# pocketwatch.net
KiCad netlist of a schematic drawn in EAGLE
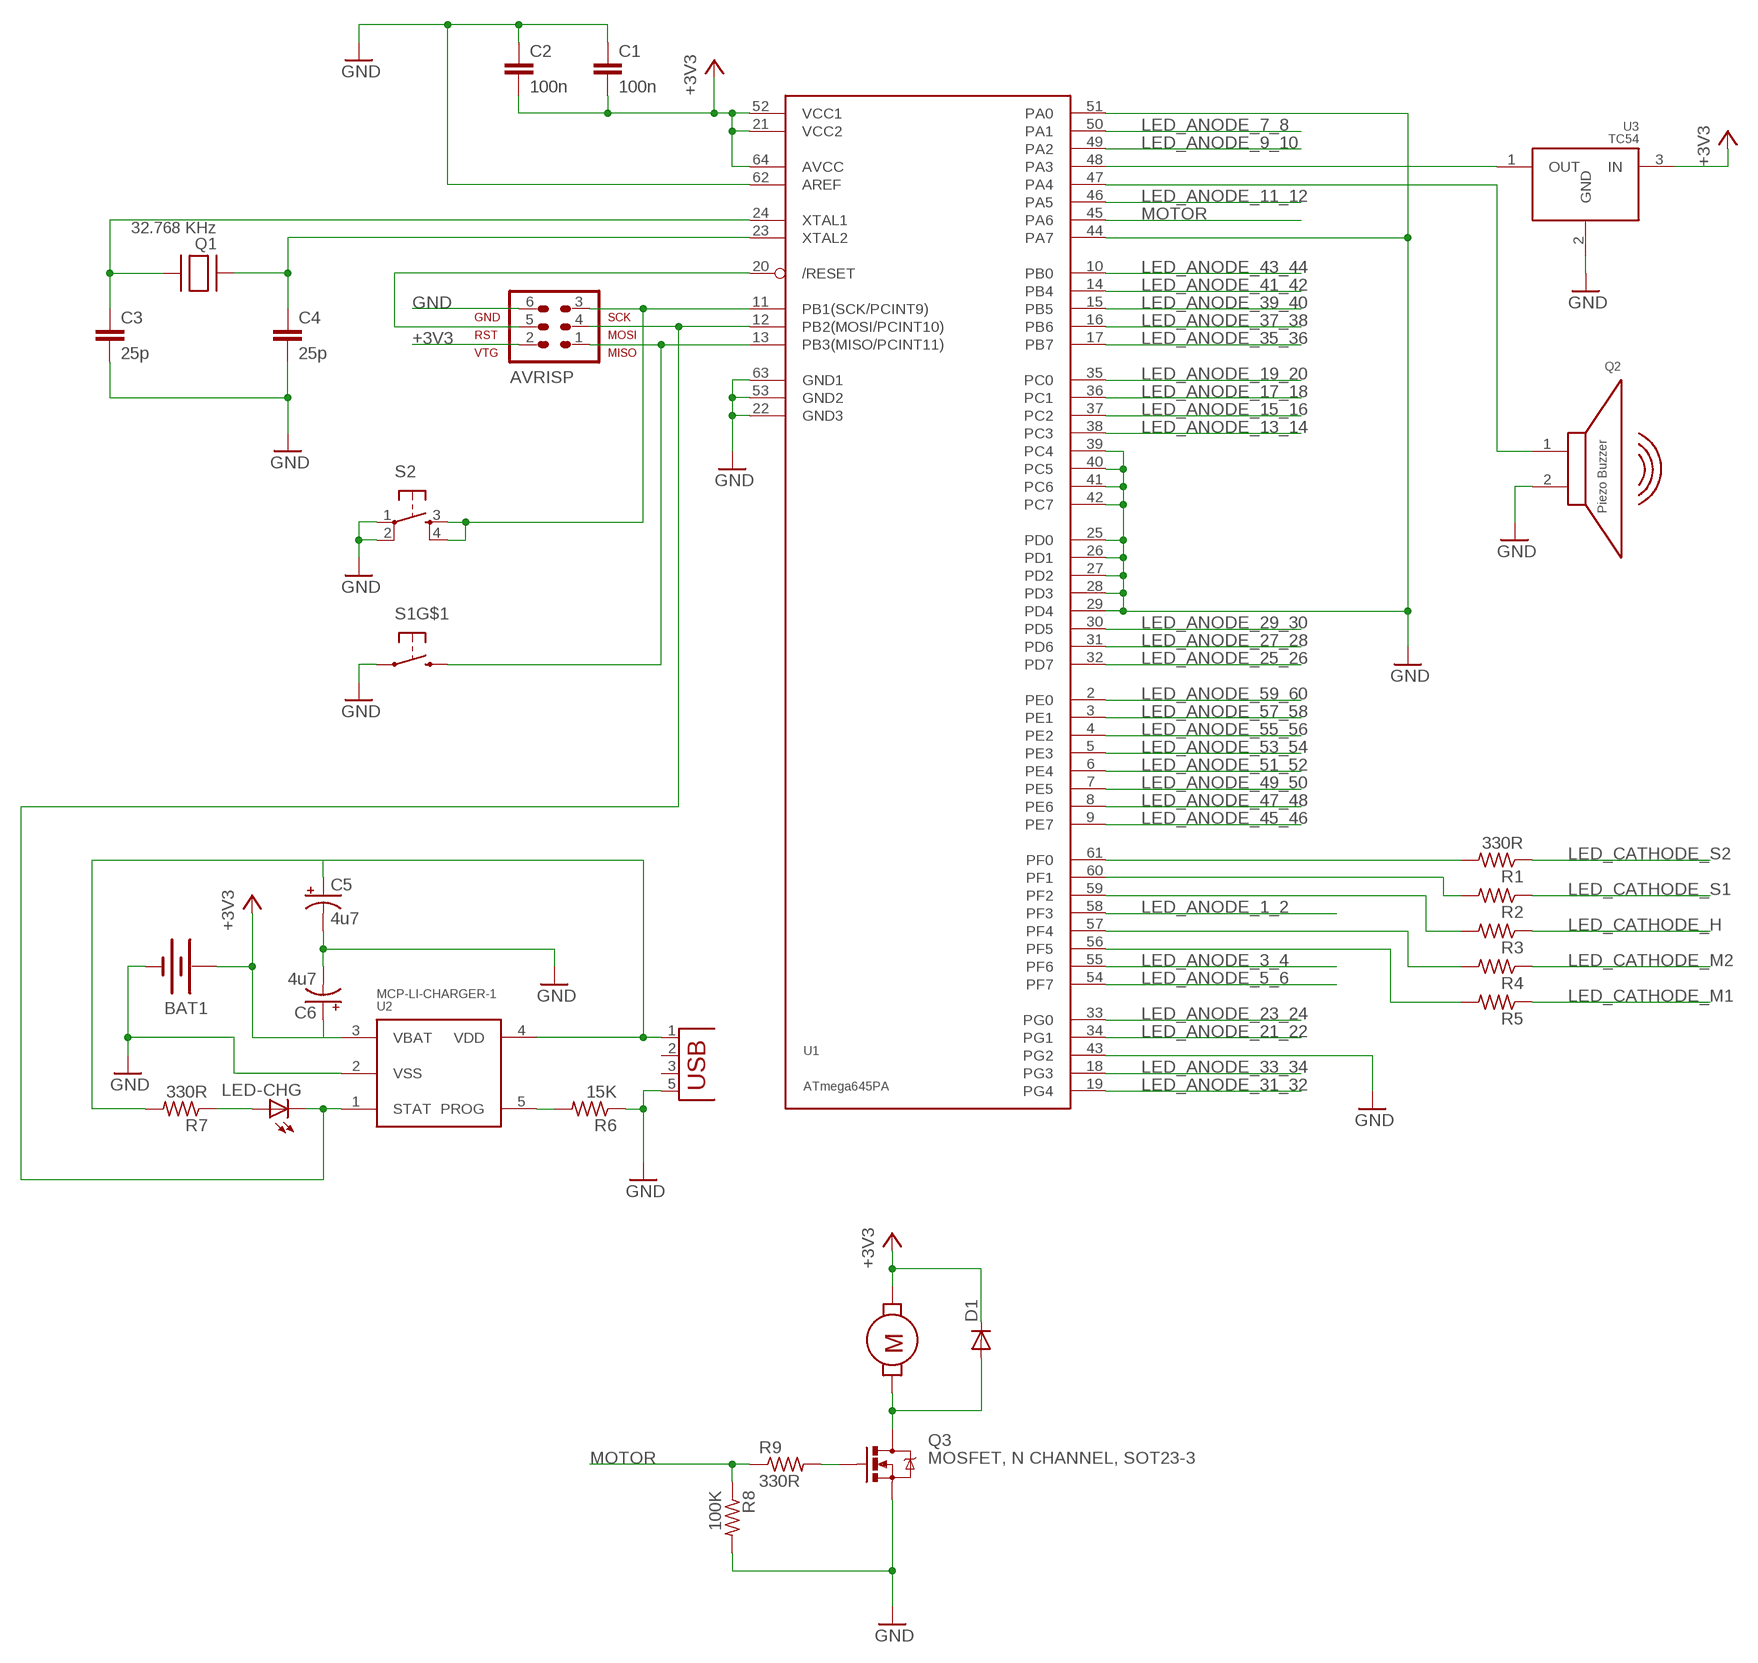
[diagram p0: schematic, sheet 1]
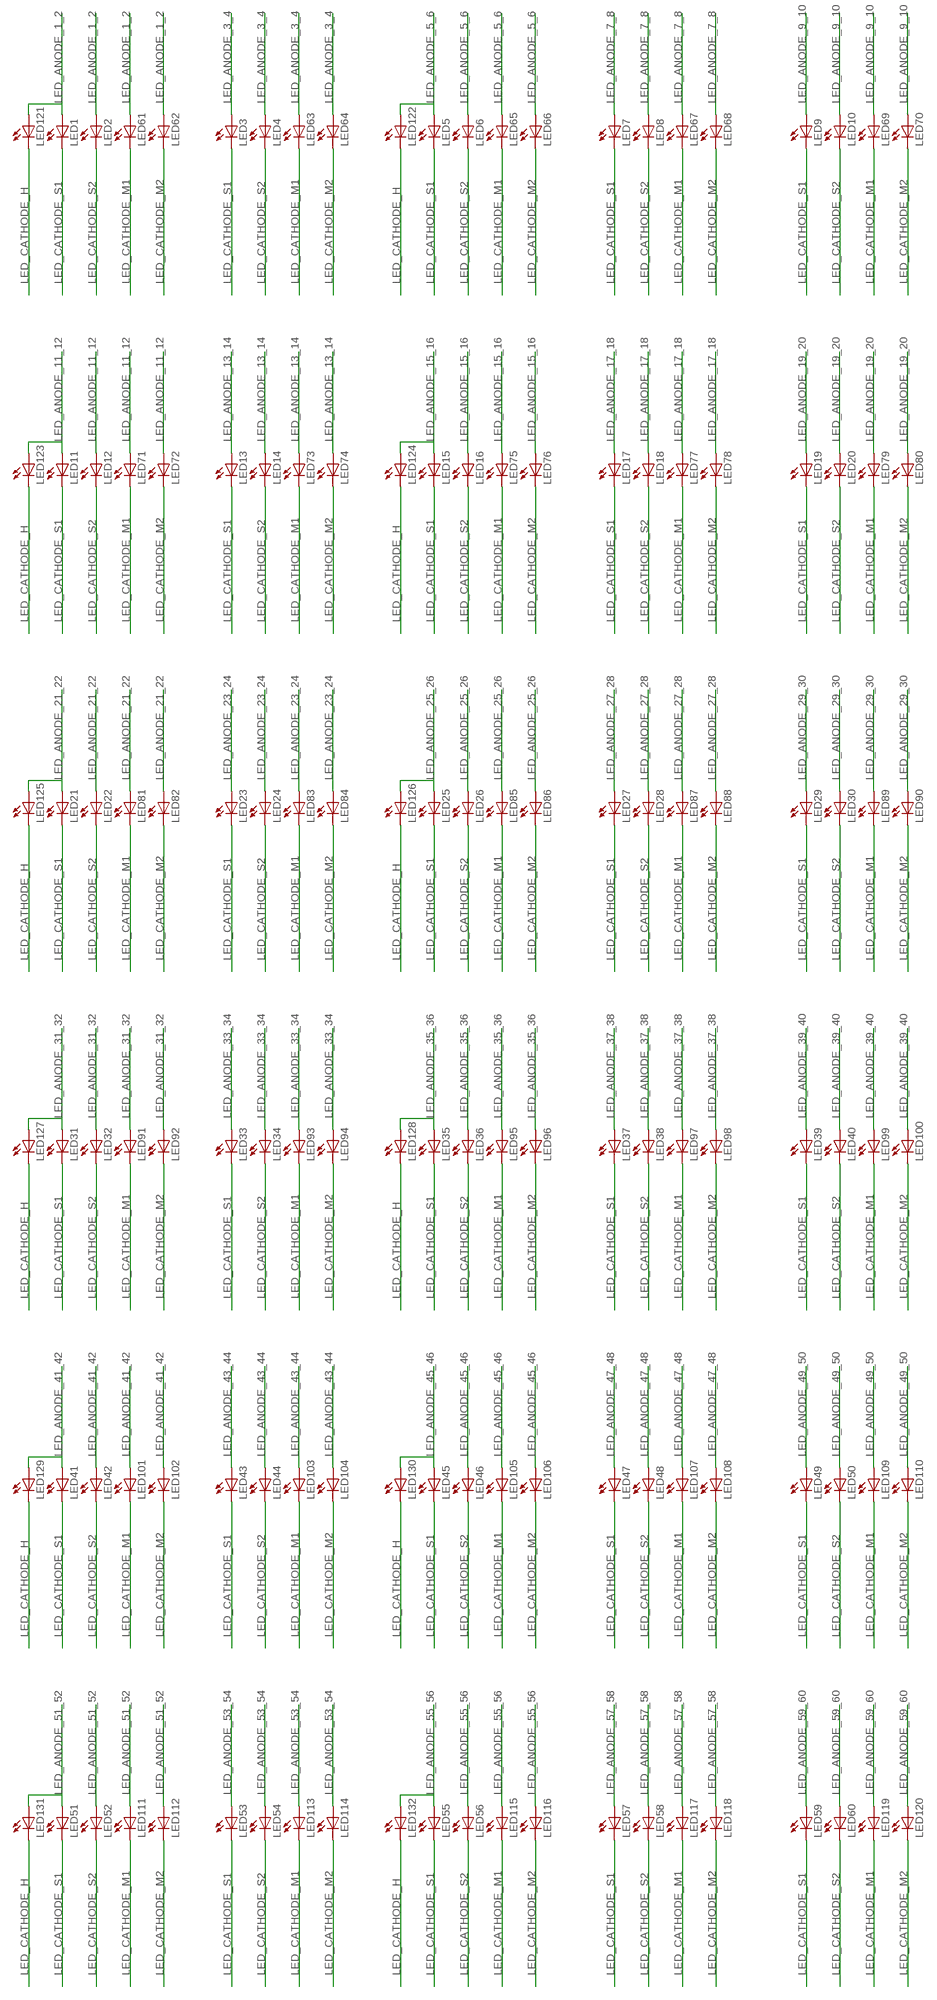
[diagram p1: schematic, sheet 2]

(export (version "E")
  (design (tool "Eeschema 10.0.6"))
  (components
    (comp (ref "LED1")
      (value "LED_CHIPLED_0603_VIA_C")
      (footprint "eagle-import:CHIPLED_0603_VIA_C")
      (libsource (lib "eagle-import") (part "LED_CHIPLED_0603_VIA_C"))
    )
    (comp (ref "LED2")
      (value "LED_CHIPLED_0603_VIA_C")
      (footprint "eagle-import:CHIPLED_0603_VIA_C")
      (libsource (lib "eagle-import") (part "LED_CHIPLED_0603_VIA_C"))
    )
    (comp (ref "LED3")
      (value "LED_CHIPLED_0603_VIA_C")
      (footprint "eagle-import:CHIPLED_0603_VIA_C")
      (libsource (lib "eagle-import") (part "LED_CHIPLED_0603_VIA_C"))
    )
    (comp (ref "LED4")
      (value "LED_CHIPLED_0603_VIA_C")
      (footprint "eagle-import:CHIPLED_0603_VIA_C")
      (libsource (lib "eagle-import") (part "LED_CHIPLED_0603_VIA_C"))
    )
    (comp (ref "LED5")
      (value "LED_CHIPLED_0603_VIA_C")
      (footprint "eagle-import:CHIPLED_0603_VIA_C")
      (libsource (lib "eagle-import") (part "LED_CHIPLED_0603_VIA_C"))
    )
    (comp (ref "LED6")
      (value "LED_CHIPLED_0603_VIA_C")
      (footprint "eagle-import:CHIPLED_0603_VIA_C")
      (libsource (lib "eagle-import") (part "LED_CHIPLED_0603_VIA_C"))
    )
    (comp (ref "LED7")
      (value "LED_CHIPLED_0603_VIA_C")
      (footprint "eagle-import:CHIPLED_0603_VIA_C")
      (libsource (lib "eagle-import") (part "LED_CHIPLED_0603_VIA_C"))
    )
    (comp (ref "LED8")
      (value "LED_CHIPLED_0603_VIA_C")
      (footprint "eagle-import:CHIPLED_0603_VIA_C")
      (libsource (lib "eagle-import") (part "LED_CHIPLED_0603_VIA_C"))
    )
    (comp (ref "LED9")
      (value "LED_CHIPLED_0603_VIA_C")
      (footprint "eagle-import:CHIPLED_0603_VIA_C")
      (libsource (lib "eagle-import") (part "LED_CHIPLED_0603_VIA_C"))
    )
    (comp (ref "LED10")
      (value "LED_CHIPLED_0603_VIA_C")
      (footprint "eagle-import:CHIPLED_0603_VIA_C")
      (libsource (lib "eagle-import") (part "LED_CHIPLED_0603_VIA_C"))
    )
    (comp (ref "LED11")
      (value "LED_CHIPLED_0603_VIA_C")
      (footprint "eagle-import:CHIPLED_0603_VIA_C")
      (libsource (lib "eagle-import") (part "LED_CHIPLED_0603_VIA_C"))
    )
    (comp (ref "LED12")
      (value "LED_CHIPLED_0603_VIA_C")
      (footprint "eagle-import:CHIPLED_0603_VIA_C")
      (libsource (lib "eagle-import") (part "LED_CHIPLED_0603_VIA_C"))
    )
    (comp (ref "LED13")
      (value "LED_CHIPLED_0603_VIA_C")
      (footprint "eagle-import:CHIPLED_0603_VIA_C")
      (libsource (lib "eagle-import") (part "LED_CHIPLED_0603_VIA_C"))
    )
    (comp (ref "LED14")
      (value "LED_CHIPLED_0603_VIA_C")
      (footprint "eagle-import:CHIPLED_0603_VIA_C")
      (libsource (lib "eagle-import") (part "LED_CHIPLED_0603_VIA_C"))
    )
    (comp (ref "LED15")
      (value "LED_CHIPLED_0603_VIA_C")
      (footprint "eagle-import:CHIPLED_0603_VIA_C")
      (libsource (lib "eagle-import") (part "LED_CHIPLED_0603_VIA_C"))
    )
    (comp (ref "LED16")
      (value "LED_CHIPLED_0603_VIA_C")
      (footprint "eagle-import:CHIPLED_0603_VIA_C")
      (libsource (lib "eagle-import") (part "LED_CHIPLED_0603_VIA_C"))
    )
    (comp (ref "LED17")
      (value "LED_CHIPLED_0603_VIA_C")
      (footprint "eagle-import:CHIPLED_0603_VIA_C")
      (libsource (lib "eagle-import") (part "LED_CHIPLED_0603_VIA_C"))
    )
    (comp (ref "LED18")
      (value "LED_CHIPLED_0603_VIA_C")
      (footprint "eagle-import:CHIPLED_0603_VIA_C")
      (libsource (lib "eagle-import") (part "LED_CHIPLED_0603_VIA_C"))
    )
    (comp (ref "LED19")
      (value "LED_CHIPLED_0603_VIA_C")
      (footprint "eagle-import:CHIPLED_0603_VIA_C")
      (libsource (lib "eagle-import") (part "LED_CHIPLED_0603_VIA_C"))
    )
    (comp (ref "LED20")
      (value "LED_CHIPLED_0603_VIA_C")
      (footprint "eagle-import:CHIPLED_0603_VIA_C")
      (libsource (lib "eagle-import") (part "LED_CHIPLED_0603_VIA_C"))
    )
    (comp (ref "LED21")
      (value "LED_CHIPLED_0603_VIA_C")
      (footprint "eagle-import:CHIPLED_0603_VIA_C")
      (libsource (lib "eagle-import") (part "LED_CHIPLED_0603_VIA_C"))
    )
    (comp (ref "LED22")
      (value "LED_CHIPLED_0603_VIA_C")
      (footprint "eagle-import:CHIPLED_0603_VIA_C")
      (libsource (lib "eagle-import") (part "LED_CHIPLED_0603_VIA_C"))
    )
    (comp (ref "LED23")
      (value "LED_CHIPLED_0603_VIA_C")
      (footprint "eagle-import:CHIPLED_0603_VIA_C")
      (libsource (lib "eagle-import") (part "LED_CHIPLED_0603_VIA_C"))
    )
    (comp (ref "LED24")
      (value "LED_CHIPLED_0603_VIA_C")
      (footprint "eagle-import:CHIPLED_0603_VIA_C")
      (libsource (lib "eagle-import") (part "LED_CHIPLED_0603_VIA_C"))
    )
    (comp (ref "LED25")
      (value "LED_CHIPLED_0603_VIA_C")
      (footprint "eagle-import:CHIPLED_0603_VIA_C")
      (libsource (lib "eagle-import") (part "LED_CHIPLED_0603_VIA_C"))
    )
    (comp (ref "LED26")
      (value "LED_CHIPLED_0603_VIA_C")
      (footprint "eagle-import:CHIPLED_0603_VIA_C")
      (libsource (lib "eagle-import") (part "LED_CHIPLED_0603_VIA_C"))
    )
    (comp (ref "LED27")
      (value "LED_CHIPLED_0603_VIA_C")
      (footprint "eagle-import:CHIPLED_0603_VIA_C")
      (libsource (lib "eagle-import") (part "LED_CHIPLED_0603_VIA_C"))
    )
    (comp (ref "LED28")
      (value "LED_CHIPLED_0603_VIA_C")
      (footprint "eagle-import:CHIPLED_0603_VIA_C")
      (libsource (lib "eagle-import") (part "LED_CHIPLED_0603_VIA_C"))
    )
    (comp (ref "LED29")
      (value "LED_CHIPLED_0603_VIA_C")
      (footprint "eagle-import:CHIPLED_0603_VIA_C")
      (libsource (lib "eagle-import") (part "LED_CHIPLED_0603_VIA_C"))
    )
    (comp (ref "LED30")
      (value "LED_CHIPLED_0603_VIA_C")
      (footprint "eagle-import:CHIPLED_0603_VIA_C")
      (libsource (lib "eagle-import") (part "LED_CHIPLED_0603_VIA_C"))
    )
    (comp (ref "LED31")
      (value "LED_CHIPLED_0603_VIA_C")
      (footprint "eagle-import:CHIPLED_0603_VIA_C")
      (libsource (lib "eagle-import") (part "LED_CHIPLED_0603_VIA_C"))
    )
    (comp (ref "LED32")
      (value "LED_CHIPLED_0603_VIA_C")
      (footprint "eagle-import:CHIPLED_0603_VIA_C")
      (libsource (lib "eagle-import") (part "LED_CHIPLED_0603_VIA_C"))
    )
    (comp (ref "LED33")
      (value "LED_CHIPLED_0603_VIA_C")
      (footprint "eagle-import:CHIPLED_0603_VIA_C")
      (libsource (lib "eagle-import") (part "LED_CHIPLED_0603_VIA_C"))
    )
    (comp (ref "LED34")
      (value "LED_CHIPLED_0603_VIA_C")
      (footprint "eagle-import:CHIPLED_0603_VIA_C")
      (libsource (lib "eagle-import") (part "LED_CHIPLED_0603_VIA_C"))
    )
    (comp (ref "LED35")
      (value "LED_CHIPLED_0603_VIA_C")
      (footprint "eagle-import:CHIPLED_0603_VIA_C")
      (libsource (lib "eagle-import") (part "LED_CHIPLED_0603_VIA_C"))
    )
    (comp (ref "LED36")
      (value "LED_CHIPLED_0603_VIA_C")
      (footprint "eagle-import:CHIPLED_0603_VIA_C")
      (libsource (lib "eagle-import") (part "LED_CHIPLED_0603_VIA_C"))
    )
    (comp (ref "LED37")
      (value "LED_CHIPLED_0603_VIA_C")
      (footprint "eagle-import:CHIPLED_0603_VIA_C")
      (libsource (lib "eagle-import") (part "LED_CHIPLED_0603_VIA_C"))
    )
    (comp (ref "LED38")
      (value "LED_CHIPLED_0603_VIA_C")
      (footprint "eagle-import:CHIPLED_0603_VIA_C")
      (libsource (lib "eagle-import") (part "LED_CHIPLED_0603_VIA_C"))
    )
    (comp (ref "LED39")
      (value "LED_CHIPLED_0603_VIA_C")
      (footprint "eagle-import:CHIPLED_0603_VIA_C")
      (libsource (lib "eagle-import") (part "LED_CHIPLED_0603_VIA_C"))
    )
    (comp (ref "LED40")
      (value "LED_CHIPLED_0603_VIA_C")
      (footprint "eagle-import:CHIPLED_0603_VIA_C")
      (libsource (lib "eagle-import") (part "LED_CHIPLED_0603_VIA_C"))
    )
    (comp (ref "LED41")
      (value "LED_CHIPLED_0603_VIA_C")
      (footprint "eagle-import:CHIPLED_0603_VIA_C")
      (libsource (lib "eagle-import") (part "LED_CHIPLED_0603_VIA_C"))
    )
    (comp (ref "LED42")
      (value "LED_CHIPLED_0603_VIA_C")
      (footprint "eagle-import:CHIPLED_0603_VIA_C")
      (libsource (lib "eagle-import") (part "LED_CHIPLED_0603_VIA_C"))
    )
    (comp (ref "LED43")
      (value "LED_CHIPLED_0603_VIA_C")
      (footprint "eagle-import:CHIPLED_0603_VIA_C")
      (libsource (lib "eagle-import") (part "LED_CHIPLED_0603_VIA_C"))
    )
    (comp (ref "LED44")
      (value "LED_CHIPLED_0603_VIA_C")
      (footprint "eagle-import:CHIPLED_0603_VIA_C")
      (libsource (lib "eagle-import") (part "LED_CHIPLED_0603_VIA_C"))
    )
    (comp (ref "LED45")
      (value "LED_CHIPLED_0603_VIA_C")
      (footprint "eagle-import:CHIPLED_0603_VIA_C")
      (libsource (lib "eagle-import") (part "LED_CHIPLED_0603_VIA_C"))
    )
    (comp (ref "LED46")
      (value "LED_CHIPLED_0603_VIA_C")
      (footprint "eagle-import:CHIPLED_0603_VIA_C")
      (libsource (lib "eagle-import") (part "LED_CHIPLED_0603_VIA_C"))
    )
    (comp (ref "LED47")
      (value "LED_CHIPLED_0603_VIA_C")
      (footprint "eagle-import:CHIPLED_0603_VIA_C")
      (libsource (lib "eagle-import") (part "LED_CHIPLED_0603_VIA_C"))
    )
    (comp (ref "LED48")
      (value "LED_CHIPLED_0603_VIA_C")
      (footprint "eagle-import:CHIPLED_0603_VIA_C")
      (libsource (lib "eagle-import") (part "LED_CHIPLED_0603_VIA_C"))
    )
    (comp (ref "LED49")
      (value "LED_CHIPLED_0603_VIA_C")
      (footprint "eagle-import:CHIPLED_0603_VIA_C")
      (libsource (lib "eagle-import") (part "LED_CHIPLED_0603_VIA_C"))
    )
    (comp (ref "LED50")
      (value "LED_CHIPLED_0603_VIA_C")
      (footprint "eagle-import:CHIPLED_0603_VIA_C")
      (libsource (lib "eagle-import") (part "LED_CHIPLED_0603_VIA_C"))
    )
    (comp (ref "LED51")
      (value "LED_CHIPLED_0603_VIA_C")
      (footprint "eagle-import:CHIPLED_0603_VIA_C")
      (libsource (lib "eagle-import") (part "LED_CHIPLED_0603_VIA_C"))
    )
    (comp (ref "LED52")
      (value "LED_CHIPLED_0603_VIA_C")
      (footprint "eagle-import:CHIPLED_0603_VIA_C")
      (libsource (lib "eagle-import") (part "LED_CHIPLED_0603_VIA_C"))
    )
    (comp (ref "LED53")
      (value "LED_CHIPLED_0603_VIA_C")
      (footprint "eagle-import:CHIPLED_0603_VIA_C")
      (libsource (lib "eagle-import") (part "LED_CHIPLED_0603_VIA_C"))
    )
    (comp (ref "LED54")
      (value "LED_CHIPLED_0603_VIA_C")
      (footprint "eagle-import:CHIPLED_0603_VIA_C")
      (libsource (lib "eagle-import") (part "LED_CHIPLED_0603_VIA_C"))
    )
    (comp (ref "LED55")
      (value "LED_CHIPLED_0603_VIA_C")
      (footprint "eagle-import:CHIPLED_0603_VIA_C")
      (libsource (lib "eagle-import") (part "LED_CHIPLED_0603_VIA_C"))
    )
    (comp (ref "LED56")
      (value "LED_CHIPLED_0603_VIA_C")
      (footprint "eagle-import:CHIPLED_0603_VIA_C")
      (libsource (lib "eagle-import") (part "LED_CHIPLED_0603_VIA_C"))
    )
    (comp (ref "LED57")
      (value "LED_CHIPLED_0603_VIA_C")
      (footprint "eagle-import:CHIPLED_0603_VIA_C")
      (libsource (lib "eagle-import") (part "LED_CHIPLED_0603_VIA_C"))
    )
    (comp (ref "LED58")
      (value "LED_CHIPLED_0603_VIA_C")
      (footprint "eagle-import:CHIPLED_0603_VIA_C")
      (libsource (lib "eagle-import") (part "LED_CHIPLED_0603_VIA_C"))
    )
    (comp (ref "LED59")
      (value "LED_CHIPLED_0603_VIA_C")
      (footprint "eagle-import:CHIPLED_0603_VIA_C")
      (libsource (lib "eagle-import") (part "LED_CHIPLED_0603_VIA_C"))
    )
    (comp (ref "LED60")
      (value "LED_CHIPLED_0603_VIA_C")
      (footprint "eagle-import:CHIPLED_0603_VIA_C")
      (libsource (lib "eagle-import") (part "LED_CHIPLED_0603_VIA_C"))
    )
    (comp (ref "LED61")
      (value "LED_CHIPLED_0603_VIA_C")
      (footprint "eagle-import:CHIPLED_0603_VIA_C")
      (libsource (lib "eagle-import") (part "LED_CHIPLED_0603_VIA_C"))
    )
    (comp (ref "LED62")
      (value "LED_CHIPLED_0603_VIA_C")
      (footprint "eagle-import:CHIPLED_0603_VIA_C")
      (libsource (lib "eagle-import") (part "LED_CHIPLED_0603_VIA_C"))
    )
    (comp (ref "LED63")
      (value "LED_CHIPLED_0603_VIA_C")
      (footprint "eagle-import:CHIPLED_0603_VIA_C")
      (libsource (lib "eagle-import") (part "LED_CHIPLED_0603_VIA_C"))
    )
    (comp (ref "LED64")
      (value "LED_CHIPLED_0603_VIA_C")
      (footprint "eagle-import:CHIPLED_0603_VIA_C")
      (libsource (lib "eagle-import") (part "LED_CHIPLED_0603_VIA_C"))
    )
    (comp (ref "LED65")
      (value "LED_CHIPLED_0603_VIA_C")
      (footprint "eagle-import:CHIPLED_0603_VIA_C")
      (libsource (lib "eagle-import") (part "LED_CHIPLED_0603_VIA_C"))
    )
    (comp (ref "LED66")
      (value "LED_CHIPLED_0603_VIA_C")
      (footprint "eagle-import:CHIPLED_0603_VIA_C")
      (libsource (lib "eagle-import") (part "LED_CHIPLED_0603_VIA_C"))
    )
    (comp (ref "LED67")
      (value "LED_CHIPLED_0603_VIA_C")
      (footprint "eagle-import:CHIPLED_0603_VIA_C")
      (libsource (lib "eagle-import") (part "LED_CHIPLED_0603_VIA_C"))
    )
    (comp (ref "LED68")
      (value "LED_CHIPLED_0603_VIA_C")
      (footprint "eagle-import:CHIPLED_0603_VIA_C")
      (libsource (lib "eagle-import") (part "LED_CHIPLED_0603_VIA_C"))
    )
    (comp (ref "LED69")
      (value "LED_CHIPLED_0603_VIA_C")
      (footprint "eagle-import:CHIPLED_0603_VIA_C")
      (libsource (lib "eagle-import") (part "LED_CHIPLED_0603_VIA_C"))
    )
    (comp (ref "LED70")
      (value "LED_CHIPLED_0603_VIA_C")
      (footprint "eagle-import:CHIPLED_0603_VIA_C")
      (libsource (lib "eagle-import") (part "LED_CHIPLED_0603_VIA_C"))
    )
    (comp (ref "LED71")
      (value "LED_CHIPLED_0603_VIA_C")
      (footprint "eagle-import:CHIPLED_0603_VIA_C")
      (libsource (lib "eagle-import") (part "LED_CHIPLED_0603_VIA_C"))
    )
    (comp (ref "LED72")
      (value "LED_CHIPLED_0603_VIA_C")
      (footprint "eagle-import:CHIPLED_0603_VIA_C")
      (libsource (lib "eagle-import") (part "LED_CHIPLED_0603_VIA_C"))
    )
    (comp (ref "LED73")
      (value "LED_CHIPLED_0603_VIA_C")
      (footprint "eagle-import:CHIPLED_0603_VIA_C")
      (libsource (lib "eagle-import") (part "LED_CHIPLED_0603_VIA_C"))
    )
    (comp (ref "LED74")
      (value "LED_CHIPLED_0603_VIA_C")
      (footprint "eagle-import:CHIPLED_0603_VIA_C")
      (libsource (lib "eagle-import") (part "LED_CHIPLED_0603_VIA_C"))
    )
    (comp (ref "LED75")
      (value "LED_CHIPLED_0603_VIA_C")
      (footprint "eagle-import:CHIPLED_0603_VIA_C")
      (libsource (lib "eagle-import") (part "LED_CHIPLED_0603_VIA_C"))
    )
    (comp (ref "LED76")
      (value "LED_CHIPLED_0603_VIA_C")
      (footprint "eagle-import:CHIPLED_0603_VIA_C")
      (libsource (lib "eagle-import") (part "LED_CHIPLED_0603_VIA_C"))
    )
    (comp (ref "LED77")
      (value "LED_CHIPLED_0603_VIA_C")
      (footprint "eagle-import:CHIPLED_0603_VIA_C")
      (libsource (lib "eagle-import") (part "LED_CHIPLED_0603_VIA_C"))
    )
    (comp (ref "LED78")
      (value "LED_CHIPLED_0603_VIA_C")
      (footprint "eagle-import:CHIPLED_0603_VIA_C")
      (libsource (lib "eagle-import") (part "LED_CHIPLED_0603_VIA_C"))
    )
    (comp (ref "LED79")
      (value "LED_CHIPLED_0603_VIA_C")
      (footprint "eagle-import:CHIPLED_0603_VIA_C")
      (libsource (lib "eagle-import") (part "LED_CHIPLED_0603_VIA_C"))
    )
    (comp (ref "LED80")
      (value "LED_CHIPLED_0603_VIA_C")
      (footprint "eagle-import:CHIPLED_0603_VIA_C")
      (libsource (lib "eagle-import") (part "LED_CHIPLED_0603_VIA_C"))
    )
    (comp (ref "LED81")
      (value "LED_CHIPLED_0603_VIA_C")
      (footprint "eagle-import:CHIPLED_0603_VIA_C")
      (libsource (lib "eagle-import") (part "LED_CHIPLED_0603_VIA_C"))
    )
    (comp (ref "LED82")
      (value "LED_CHIPLED_0603_VIA_C")
      (footprint "eagle-import:CHIPLED_0603_VIA_C")
      (libsource (lib "eagle-import") (part "LED_CHIPLED_0603_VIA_C"))
    )
    (comp (ref "LED83")
      (value "LED_CHIPLED_0603_VIA_C")
      (footprint "eagle-import:CHIPLED_0603_VIA_C")
      (libsource (lib "eagle-import") (part "LED_CHIPLED_0603_VIA_C"))
    )
    (comp (ref "LED84")
      (value "LED_CHIPLED_0603_VIA_C")
      (footprint "eagle-import:CHIPLED_0603_VIA_C")
      (libsource (lib "eagle-import") (part "LED_CHIPLED_0603_VIA_C"))
    )
    (comp (ref "LED85")
      (value "LED_CHIPLED_0603_VIA_C")
      (footprint "eagle-import:CHIPLED_0603_VIA_C")
      (libsource (lib "eagle-import") (part "LED_CHIPLED_0603_VIA_C"))
    )
    (comp (ref "LED86")
      (value "LED_CHIPLED_0603_VIA_C")
      (footprint "eagle-import:CHIPLED_0603_VIA_C")
      (libsource (lib "eagle-import") (part "LED_CHIPLED_0603_VIA_C"))
    )
    (comp (ref "LED87")
      (value "LED_CHIPLED_0603_VIA_C")
      (footprint "eagle-import:CHIPLED_0603_VIA_C")
      (libsource (lib "eagle-import") (part "LED_CHIPLED_0603_VIA_C"))
    )
    (comp (ref "LED88")
      (value "LED_CHIPLED_0603_VIA_C")
      (footprint "eagle-import:CHIPLED_0603_VIA_C")
      (libsource (lib "eagle-import") (part "LED_CHIPLED_0603_VIA_C"))
    )
    (comp (ref "LED89")
      (value "LED_CHIPLED_0603_VIA_C")
      (footprint "eagle-import:CHIPLED_0603_VIA_C")
      (libsource (lib "eagle-import") (part "LED_CHIPLED_0603_VIA_C"))
    )
    (comp (ref "LED90")
      (value "LED_CHIPLED_0603_VIA_C")
      (footprint "eagle-import:CHIPLED_0603_VIA_C")
      (libsource (lib "eagle-import") (part "LED_CHIPLED_0603_VIA_C"))
    )
    (comp (ref "LED91")
      (value "LED_CHIPLED_0603_VIA_C")
      (footprint "eagle-import:CHIPLED_0603_VIA_C")
      (libsource (lib "eagle-import") (part "LED_CHIPLED_0603_VIA_C"))
    )
    (comp (ref "LED92")
      (value "LED_CHIPLED_0603_VIA_C")
      (footprint "eagle-import:CHIPLED_0603_VIA_C")
      (libsource (lib "eagle-import") (part "LED_CHIPLED_0603_VIA_C"))
    )
    (comp (ref "LED93")
      (value "LED_CHIPLED_0603_VIA_C")
      (footprint "eagle-import:CHIPLED_0603_VIA_C")
      (libsource (lib "eagle-import") (part "LED_CHIPLED_0603_VIA_C"))
    )
    (comp (ref "LED94")
      (value "LED_CHIPLED_0603_VIA_C")
      (footprint "eagle-import:CHIPLED_0603_VIA_C")
      (libsource (lib "eagle-import") (part "LED_CHIPLED_0603_VIA_C"))
    )
    (comp (ref "LED95")
      (value "LED_CHIPLED_0603_VIA_C")
      (footprint "eagle-import:CHIPLED_0603_VIA_C")
      (libsource (lib "eagle-import") (part "LED_CHIPLED_0603_VIA_C"))
    )
    (comp (ref "LED96")
      (value "LED_CHIPLED_0603_VIA_C")
      (footprint "eagle-import:CHIPLED_0603_VIA_C")
      (libsource (lib "eagle-import") (part "LED_CHIPLED_0603_VIA_C"))
    )
    (comp (ref "LED97")
      (value "LED_CHIPLED_0603_VIA_C")
      (footprint "eagle-import:CHIPLED_0603_VIA_C")
      (libsource (lib "eagle-import") (part "LED_CHIPLED_0603_VIA_C"))
    )
    (comp (ref "LED98")
      (value "LED_CHIPLED_0603_VIA_C")
      (footprint "eagle-import:CHIPLED_0603_VIA_C")
      (libsource (lib "eagle-import") (part "LED_CHIPLED_0603_VIA_C"))
    )
    (comp (ref "LED99")
      (value "LED_CHIPLED_0603_VIA_C")
      (footprint "eagle-import:CHIPLED_0603_VIA_C")
      (libsource (lib "eagle-import") (part "LED_CHIPLED_0603_VIA_C"))
    )
    (comp (ref "LED100")
      (value "LED_CHIPLED_0603_VIA_C")
      (footprint "eagle-import:CHIPLED_0603_VIA_C")
      (libsource (lib "eagle-import") (part "LED_CHIPLED_0603_VIA_C"))
    )
    (comp (ref "LED101")
      (value "LED_CHIPLED_0603_VIA_C")
      (footprint "eagle-import:CHIPLED_0603_VIA_C")
      (libsource (lib "eagle-import") (part "LED_CHIPLED_0603_VIA_C"))
    )
    (comp (ref "LED102")
      (value "LED_CHIPLED_0603_VIA_C")
      (footprint "eagle-import:CHIPLED_0603_VIA_C")
      (libsource (lib "eagle-import") (part "LED_CHIPLED_0603_VIA_C"))
    )
    (comp (ref "LED103")
      (value "LED_CHIPLED_0603_VIA_C")
      (footprint "eagle-import:CHIPLED_0603_VIA_C")
      (libsource (lib "eagle-import") (part "LED_CHIPLED_0603_VIA_C"))
    )
    (comp (ref "LED104")
      (value "LED_CHIPLED_0603_VIA_C")
      (footprint "eagle-import:CHIPLED_0603_VIA_C")
      (libsource (lib "eagle-import") (part "LED_CHIPLED_0603_VIA_C"))
    )
    (comp (ref "LED105")
      (value "LED_CHIPLED_0603_VIA_C")
      (footprint "eagle-import:CHIPLED_0603_VIA_C")
      (libsource (lib "eagle-import") (part "LED_CHIPLED_0603_VIA_C"))
    )
    (comp (ref "LED106")
      (value "LED_CHIPLED_0603_VIA_C")
      (footprint "eagle-import:CHIPLED_0603_VIA_C")
      (libsource (lib "eagle-import") (part "LED_CHIPLED_0603_VIA_C"))
    )
    (comp (ref "LED107")
      (value "LED_CHIPLED_0603_VIA_C")
      (footprint "eagle-import:CHIPLED_0603_VIA_C")
      (libsource (lib "eagle-import") (part "LED_CHIPLED_0603_VIA_C"))
    )
    (comp (ref "LED108")
      (value "LED_CHIPLED_0603_VIA_C")
      (footprint "eagle-import:CHIPLED_0603_VIA_C")
      (libsource (lib "eagle-import") (part "LED_CHIPLED_0603_VIA_C"))
    )
    (comp (ref "LED109")
      (value "LED_CHIPLED_0603_VIA_C")
      (footprint "eagle-import:CHIPLED_0603_VIA_C")
      (libsource (lib "eagle-import") (part "LED_CHIPLED_0603_VIA_C"))
    )
    (comp (ref "LED110")
      (value "LED_CHIPLED_0603_VIA_C")
      (footprint "eagle-import:CHIPLED_0603_VIA_C")
      (libsource (lib "eagle-import") (part "LED_CHIPLED_0603_VIA_C"))
    )
    (comp (ref "LED111")
      (value "LED_CHIPLED_0603_VIA_C")
      (footprint "eagle-import:CHIPLED_0603_VIA_C")
      (libsource (lib "eagle-import") (part "LED_CHIPLED_0603_VIA_C"))
    )
    (comp (ref "LED112")
      (value "LED_CHIPLED_0603_VIA_C")
      (footprint "eagle-import:CHIPLED_0603_VIA_C")
      (libsource (lib "eagle-import") (part "LED_CHIPLED_0603_VIA_C"))
    )
    (comp (ref "LED113")
      (value "LED_CHIPLED_0603_VIA_C")
      (footprint "eagle-import:CHIPLED_0603_VIA_C")
      (libsource (lib "eagle-import") (part "LED_CHIPLED_0603_VIA_C"))
    )
    (comp (ref "LED114")
      (value "LED_CHIPLED_0603_VIA_C")
      (footprint "eagle-import:CHIPLED_0603_VIA_C")
      (libsource (lib "eagle-import") (part "LED_CHIPLED_0603_VIA_C"))
    )
    (comp (ref "LED115")
      (value "LED_CHIPLED_0603_VIA_C")
      (footprint "eagle-import:CHIPLED_0603_VIA_C")
      (libsource (lib "eagle-import") (part "LED_CHIPLED_0603_VIA_C"))
    )
    (comp (ref "LED116")
      (value "LED_CHIPLED_0603_VIA_C")
      (footprint "eagle-import:CHIPLED_0603_VIA_C")
      (libsource (lib "eagle-import") (part "LED_CHIPLED_0603_VIA_C"))
    )
    (comp (ref "LED117")
      (value "LED_CHIPLED_0603_VIA_C")
      (footprint "eagle-import:CHIPLED_0603_VIA_C")
      (libsource (lib "eagle-import") (part "LED_CHIPLED_0603_VIA_C"))
    )
    (comp (ref "LED118")
      (value "LED_CHIPLED_0603_VIA_C")
      (footprint "eagle-import:CHIPLED_0603_VIA_C")
      (libsource (lib "eagle-import") (part "LED_CHIPLED_0603_VIA_C"))
    )
    (comp (ref "LED119")
      (value "LED_CHIPLED_0603_VIA_C")
      (footprint "eagle-import:CHIPLED_0603_VIA_C")
      (libsource (lib "eagle-import") (part "LED_CHIPLED_0603_VIA_C"))
    )
    (comp (ref "LED120")
      (value "LED_CHIPLED_0603_VIA_C")
      (footprint "eagle-import:CHIPLED_0603_VIA_C")
      (libsource (lib "eagle-import") (part "LED_CHIPLED_0603_VIA_C"))
    )
    (comp (ref "LED121")
      (value "LED_CHIPLED_0603_VIA_C")
      (footprint "eagle-import:CHIPLED_0603_VIA_C")
      (libsource (lib "eagle-import") (part "LED_CHIPLED_0603_VIA_C"))
    )
    (comp (ref "LED122")
      (value "LED_CHIPLED_0603_VIA_C")
      (footprint "eagle-import:CHIPLED_0603_VIA_C")
      (libsource (lib "eagle-import") (part "LED_CHIPLED_0603_VIA_C"))
    )
    (comp (ref "LED123")
      (value "LED_CHIPLED_0603_VIA_C")
      (footprint "eagle-import:CHIPLED_0603_VIA_C")
      (libsource (lib "eagle-import") (part "LED_CHIPLED_0603_VIA_C"))
    )
    (comp (ref "LED124")
      (value "LED_CHIPLED_0603_VIA_C")
      (footprint "eagle-import:CHIPLED_0603_VIA_C")
      (libsource (lib "eagle-import") (part "LED_CHIPLED_0603_VIA_C"))
    )
    (comp (ref "LED125")
      (value "LED_CHIPLED_0603_VIA_C")
      (footprint "eagle-import:CHIPLED_0603_VIA_C")
      (libsource (lib "eagle-import") (part "LED_CHIPLED_0603_VIA_C"))
    )
    (comp (ref "LED126")
      (value "LED_CHIPLED_0603_VIA_C")
      (footprint "eagle-import:CHIPLED_0603_VIA_C")
      (libsource (lib "eagle-import") (part "LED_CHIPLED_0603_VIA_C"))
    )
    (comp (ref "LED127")
      (value "LED_CHIPLED_0603_VIA_C")
      (footprint "eagle-import:CHIPLED_0603_VIA_C")
      (libsource (lib "eagle-import") (part "LED_CHIPLED_0603_VIA_C"))
    )
    (comp (ref "LED128")
      (value "LED_CHIPLED_0603_VIA_C")
      (footprint "eagle-import:CHIPLED_0603_VIA_C")
      (libsource (lib "eagle-import") (part "LED_CHIPLED_0603_VIA_C"))
    )
    (comp (ref "LED129")
      (value "LED_CHIPLED_0603_VIA_C")
      (footprint "eagle-import:CHIPLED_0603_VIA_C")
      (libsource (lib "eagle-import") (part "LED_CHIPLED_0603_VIA_C"))
    )
    (comp (ref "LED130")
      (value "LED_CHIPLED_0603_VIA_C")
      (footprint "eagle-import:CHIPLED_0603_VIA_C")
      (libsource (lib "eagle-import") (part "LED_CHIPLED_0603_VIA_C"))
    )
    (comp (ref "LED131")
      (value "LED_CHIPLED_0603_VIA_C")
      (footprint "eagle-import:CHIPLED_0603_VIA_C")
      (libsource (lib "eagle-import") (part "LED_CHIPLED_0603_VIA_C"))
    )
    (comp (ref "LED132")
      (value "LED_CHIPLED_0603_VIA_C")
      (footprint "eagle-import:CHIPLED_0603_VIA_C")
      (libsource (lib "eagle-import") (part "LED_CHIPLED_0603_VIA_C"))
    )
    (comp (ref "AVRISP")
      (value "AVR-ISP-6")
      (footprint "eagle-import:AVR-ISP-6")
      (libsource (lib "eagle-import") (part "AVR-ISP-6"))
    )
    (comp (ref "BAT1")
      (value "BATTERY245MM")
      (footprint "eagle-import:BATTCON_245MM")
      (libsource (lib "eagle-import") (part "BATTERY245MM"))
    )
    (comp (ref "C1")
      (value "100n")
      (footprint "eagle-import:C0603")
      (libsource (lib "eagle-import") (part "C-EUC0603"))
    )
    (comp (ref "C2")
      (value "100n")
      (footprint "eagle-import:C0603")
      (libsource (lib "eagle-import") (part "C-EUC0603"))
    )
    (comp (ref "C3")
      (value "25p")
      (footprint "eagle-import:C0603")
      (libsource (lib "eagle-import") (part "C-EUC0603"))
    )
    (comp (ref "C4")
      (value "25p")
      (footprint "eagle-import:C0603")
      (libsource (lib "eagle-import") (part "C-EUC0603"))
    )
    (comp (ref "C5")
      (value "4u7")
      (footprint "eagle-import:SMC_A")
      (libsource (lib "eagle-import") (part "CPOL-USSMCA"))
    )
    (comp (ref "C6")
      (value "4u7")
      (footprint "eagle-import:SMC_A")
      (libsource (lib "eagle-import") (part "CPOL-USSMCA"))
    )
    (comp (ref "D1")
      (value "DIODESOD")
      (footprint "eagle-import:SOD-323")
      (libsource (lib "eagle-import") (part "DIODESOD"))
    )
    (comp (ref "LED-CHG")
      (value "LEDCHIPLED_0603")
      (footprint "eagle-import:CHIPLED_0603")
      (libsource (lib "eagle-import") (part "LEDCHIPLED_0603"))
    )
    (comp (ref "M1")
      (value "MOTOR")
      (footprint "eagle-import:VIBRATION-MOTOR")
      (libsource (lib "eagle-import") (part "MOTOR"))
    )
    (comp (ref "Q1")
      (value "32.768 KHz")
      (footprint "eagle-import:XTAL_2SMD")
      (libsource (lib "eagle-import") (part "XTALSMD1"))
    )
    (comp (ref "Q2")
      (value "BUZZER")
      (footprint "eagle-import:BUZZER_1")
      (libsource (lib "eagle-import") (part "BUZZER"))
    )
    (comp (ref "Q3")
      (value "MOSFET, N CHANNEL, SOT23-3")
      (footprint "eagle-import:SOT23-3")
      (libsource (lib "eagle-import") (part "MOSFET-NCHANNELSMD"))
    )
    (comp (ref "R1")
      (value "330R")
      (footprint "eagle-import:R0603")
      (libsource (lib "eagle-import") (part "R-US_R0603"))
    )
    (comp (ref "R2")
      (value "R-US_R0603")
      (footprint "eagle-import:R0603")
      (libsource (lib "eagle-import") (part "R-US_R0603"))
    )
    (comp (ref "R3")
      (value "R-US_R0603")
      (footprint "eagle-import:R0603")
      (libsource (lib "eagle-import") (part "R-US_R0603"))
    )
    (comp (ref "R4")
      (value "R-US_R0603")
      (footprint "eagle-import:R0603")
      (libsource (lib "eagle-import") (part "R-US_R0603"))
    )
    (comp (ref "R5")
      (value "R-US_R0603")
      (footprint "eagle-import:R0603")
      (libsource (lib "eagle-import") (part "R-US_R0603"))
    )
    (comp (ref "R6")
      (value "15K")
      (footprint "eagle-import:R0603")
      (libsource (lib "eagle-import") (part "R-US_R0603"))
    )
    (comp (ref "R7")
      (value "330R")
      (footprint "eagle-import:R0603")
      (libsource (lib "eagle-import") (part "R-US_R0603"))
    )
    (comp (ref "R8")
      (value "100K")
      (footprint "eagle-import:R0603")
      (libsource (lib "eagle-import") (part "R-US_R0603"))
    )
    (comp (ref "R9")
      (value "330R")
      (footprint "eagle-import:R0603")
      (libsource (lib "eagle-import") (part "R-US_R0603"))
    )
    (comp (ref "S1")
      (value "TAC_SWITCH_SINGLE")
      (footprint "eagle-import:TAC_SWITCH_SIDE_1")
      (libsource (lib "eagle-import") (part "TAC_SWITCH_SINGLE"))
    )
    (comp (ref "S2")
      (value "TAC_SWITCHSMD")
      (footprint "eagle-import:TACTILE_SWITCH_SMD")
      (libsource (lib "eagle-import") (part "TAC_SWITCHSMD"))
    )
    (comp (ref "U1")
      (value "ATmega645PA")
      (footprint "eagle-import:TQFP64")
      (libsource (lib "eagle-import") (part "ATMEGA645TQFP64"))
    )
    (comp (ref "U2")
      (value "MCP-LI-CHARGER-1")
      (footprint "eagle-import:SOT23-5")
      (libsource (lib "eagle-import") (part "MCP-LI-CHARGER-1"))
    )
    (comp (ref "U3")
      (value "TC54")
      (footprint "eagle-import:SOT23-3")
      (libsource (lib "eagle-import") (part "TC54"))
    )
    (comp (ref "X1")
      (value "USB-MICRO_B")
      (footprint "eagle-import:USB_MICRO_B")
      (libsource (lib "eagle-import") (part "USB-MICRO_B"))
    )
  )
  (nets
    (net (code "1") (name "+3V3") (class "Default")
      (node (ref "AVRISP") (pin "2") (pinfunction "VTG_2") (pintype "passive"))
      (node (ref "BAT1") (pin "1") (pinfunction "+_1") (pintype "power_in"))
      (node (ref "C1") (pin "2") (pinfunction "2_2") (pintype "passive"))
      (node (ref "C2") (pin "2") (pinfunction "2_2") (pintype "passive"))
      (node (ref "C6") (pin "+") (pinfunction "+_+") (pintype "passive"))
      (node (ref "D1") (pin "1") (pinfunction "C_1") (pintype "passive"))
      (node (ref "M1") (pin "P$1") (pinfunction "P$1_P$1") (pintype "bidirectional"))
      (node (ref "U1") (pin "21") (pinfunction "VCC2_21") (pintype "power_in"))
      (node (ref "U1") (pin "52") (pinfunction "VCC1_52") (pintype "power_in"))
      (node (ref "U1") (pin "64") (pinfunction "AVCC_64") (pintype "power_in"))
      (node (ref "U2") (pin "3") (pinfunction "VBAT_3") (pintype "power_in"))
      (node (ref "U3") (pin "3") (pinfunction "IN_3") (pintype "bidirectional"))
    )
    (net (code "2") (name "GND") (class "Default")
      (node (ref "AVRISP") (pin "6") (pinfunction "GND_6") (pintype "passive"))
      (node (ref "BAT1") (pin "2") (pinfunction "-_2") (pintype "power_in"))
      (node (ref "C1") (pin "1") (pinfunction "1_1") (pintype "passive"))
      (node (ref "C2") (pin "1") (pinfunction "1_1") (pintype "passive"))
      (node (ref "C3") (pin "2") (pinfunction "2_2") (pintype "passive"))
      (node (ref "C4") (pin "2") (pinfunction "2_2") (pintype "passive"))
      (node (ref "C5") (pin "-") (pinfunction "-_-") (pintype "passive"))
      (node (ref "C6") (pin "-") (pinfunction "-_-") (pintype "passive"))
      (node (ref "Q2") (pin "2") (pinfunction "P$2_2") (pintype "bidirectional"))
      (node (ref "Q3") (pin "2") (pinfunction "S_2") (pintype "passive"))
      (node (ref "R6") (pin "1") (pinfunction "1_1") (pintype "passive"))
      (node (ref "R8") (pin "2") (pinfunction "2_2") (pintype "passive"))
      (node (ref "S1") (pin "G1") (pinfunction "P$1_G1") (pintype "bidirectional"))
      (node (ref "S1") (pin "G2") (pinfunction "P$1_G2") (pintype "bidirectional"))
      (node (ref "S1") (pin "P$2") (pinfunction "1_P$2") (pintype "passive"))
      (node (ref "S2") (pin "1") (pinfunction "1_1") (pintype "passive"))
      (node (ref "S2") (pin "2") (pinfunction "2_2") (pintype "passive"))
      (node (ref "U1") (pin "22") (pinfunction "GND3_22") (pintype "power_in"))
      (node (ref "U1") (pin "25") (pinfunction "PD0_25") (pintype "bidirectional"))
      (node (ref "U1") (pin "26") (pinfunction "PD1_26") (pintype "bidirectional"))
      (node (ref "U1") (pin "27") (pinfunction "PD2_27") (pintype "bidirectional"))
      (node (ref "U1") (pin "28") (pinfunction "PD3_28") (pintype "bidirectional"))
      (node (ref "U1") (pin "29") (pinfunction "PD4_29") (pintype "bidirectional"))
      (node (ref "U1") (pin "39") (pinfunction "PC4_39") (pintype "bidirectional"))
      (node (ref "U1") (pin "40") (pinfunction "PC5_40") (pintype "bidirectional"))
      (node (ref "U1") (pin "41") (pinfunction "PC6_41") (pintype "bidirectional"))
      (node (ref "U1") (pin "42") (pinfunction "PC7_42") (pintype "bidirectional"))
      (node (ref "U1") (pin "43") (pinfunction "PG2_43") (pintype "bidirectional"))
      (node (ref "U1") (pin "44") (pinfunction "PA7_44") (pintype "bidirectional"))
      (node (ref "U1") (pin "51") (pinfunction "PA0_51") (pintype "bidirectional"))
      (node (ref "U1") (pin "53") (pinfunction "GND2_53") (pintype "power_in"))
      (node (ref "U1") (pin "62") (pinfunction "AREF_62") (pintype "power_in"))
      (node (ref "U1") (pin "63") (pinfunction "GND1_63") (pintype "power_in"))
      (node (ref "U2") (pin "2") (pinfunction "VSS_2") (pintype "power_in"))
      (node (ref "U3") (pin "2") (pinfunction "GND_2") (pintype "bidirectional"))
      (node (ref "X1") (pin "5") (pinfunction "GND_5") (pintype "bidirectional"))
      (node (ref "X1") (pin "P$3") (pinfunction "P$1_P$3") (pintype "bidirectional"))
      (node (ref "X1") (pin "P$4") (pinfunction "P$1_P$4") (pintype "bidirectional"))
      (node (ref "X1") (pin "P$7") (pinfunction "P$1_P$7") (pintype "bidirectional"))
      (node (ref "X1") (pin "P$8") (pinfunction "P$1_P$8") (pintype "bidirectional"))
    )
    (net (code "3") (name "LED_ANODE_1_2") (class "Default")
      (node (ref "LED1") (pin "A") (pinfunction "A_A") (pintype "passive"))
      (node (ref "LED121") (pin "A") (pinfunction "A_A") (pintype "passive"))
      (node (ref "LED2") (pin "A") (pinfunction "A_A") (pintype "passive"))
      (node (ref "LED61") (pin "A") (pinfunction "A_A") (pintype "passive"))
      (node (ref "LED62") (pin "A") (pinfunction "A_A") (pintype "passive"))
      (node (ref "U1") (pin "58") (pinfunction "PF3_58") (pintype "bidirectional"))
    )
    (net (code "4") (name "LED_ANODE_3_4") (class "Default")
      (node (ref "LED3") (pin "A") (pinfunction "A_A") (pintype "passive"))
      (node (ref "LED4") (pin "A") (pinfunction "A_A") (pintype "passive"))
      (node (ref "LED63") (pin "A") (pinfunction "A_A") (pintype "passive"))
      (node (ref "LED64") (pin "A") (pinfunction "A_A") (pintype "passive"))
      (node (ref "U1") (pin "55") (pinfunction "PF6_55") (pintype "bidirectional"))
    )
    (net (code "5") (name "LED_ANODE_5_6") (class "Default")
      (node (ref "LED122") (pin "A") (pinfunction "A_A") (pintype "passive"))
      (node (ref "LED5") (pin "A") (pinfunction "A_A") (pintype "passive"))
      (node (ref "LED6") (pin "A") (pinfunction "A_A") (pintype "passive"))
      (node (ref "LED65") (pin "A") (pinfunction "A_A") (pintype "passive"))
      (node (ref "LED66") (pin "A") (pinfunction "A_A") (pintype "passive"))
      (node (ref "U1") (pin "54") (pinfunction "PF7_54") (pintype "bidirectional"))
    )
    (net (code "6") (name "LED_ANODE_7_8") (class "Default")
      (node (ref "LED67") (pin "A") (pinfunction "A_A") (pintype "passive"))
      (node (ref "LED68") (pin "A") (pinfunction "A_A") (pintype "passive"))
      (node (ref "LED7") (pin "A") (pinfunction "A_A") (pintype "passive"))
      (node (ref "LED8") (pin "A") (pinfunction "A_A") (pintype "passive"))
      (node (ref "U1") (pin "50") (pinfunction "PA1_50") (pintype "bidirectional"))
    )
    (net (code "7") (name "LED_ANODE_9_10") (class "Default")
      (node (ref "LED10") (pin "A") (pinfunction "A_A") (pintype "passive"))
      (node (ref "LED69") (pin "A") (pinfunction "A_A") (pintype "passive"))
      (node (ref "LED70") (pin "A") (pinfunction "A_A") (pintype "passive"))
      (node (ref "LED9") (pin "A") (pinfunction "A_A") (pintype "passive"))
      (node (ref "U1") (pin "49") (pinfunction "PA2_49") (pintype "bidirectional"))
    )
    (net (code "8") (name "LED_ANODE_11_12") (class "Default")
      (node (ref "LED11") (pin "A") (pinfunction "A_A") (pintype "passive"))
      (node (ref "LED12") (pin "A") (pinfunction "A_A") (pintype "passive"))
      (node (ref "LED123") (pin "A") (pinfunction "A_A") (pintype "passive"))
      (node (ref "LED71") (pin "A") (pinfunction "A_A") (pintype "passive"))
      (node (ref "LED72") (pin "A") (pinfunction "A_A") (pintype "passive"))
      (node (ref "U1") (pin "46") (pinfunction "PA5_46") (pintype "bidirectional"))
    )
    (net (code "9") (name "LED_ANODE_13_14") (class "Default")
      (node (ref "LED13") (pin "A") (pinfunction "A_A") (pintype "passive"))
      (node (ref "LED14") (pin "A") (pinfunction "A_A") (pintype "passive"))
      (node (ref "LED73") (pin "A") (pinfunction "A_A") (pintype "passive"))
      (node (ref "LED74") (pin "A") (pinfunction "A_A") (pintype "passive"))
      (node (ref "U1") (pin "38") (pinfunction "PC3_38") (pintype "bidirectional"))
    )
    (net (code "10") (name "LED_ANODE_15_16") (class "Default")
      (node (ref "LED124") (pin "A") (pinfunction "A_A") (pintype "passive"))
      (node (ref "LED15") (pin "A") (pinfunction "A_A") (pintype "passive"))
      (node (ref "LED16") (pin "A") (pinfunction "A_A") (pintype "passive"))
      (node (ref "LED75") (pin "A") (pinfunction "A_A") (pintype "passive"))
      (node (ref "LED76") (pin "A") (pinfunction "A_A") (pintype "passive"))
      (node (ref "U1") (pin "37") (pinfunction "PC2_37") (pintype "bidirectional"))
    )
    (net (code "11") (name "LED_ANODE_17_18") (class "Default")
      (node (ref "LED17") (pin "A") (pinfunction "A_A") (pintype "passive"))
      (node (ref "LED18") (pin "A") (pinfunction "A_A") (pintype "passive"))
      (node (ref "LED77") (pin "A") (pinfunction "A_A") (pintype "passive"))
      (node (ref "LED78") (pin "A") (pinfunction "A_A") (pintype "passive"))
      (node (ref "U1") (pin "36") (pinfunction "PC1_36") (pintype "bidirectional"))
    )
    (net (code "12") (name "LED_ANODE_19_20") (class "Default")
      (node (ref "LED19") (pin "A") (pinfunction "A_A") (pintype "passive"))
      (node (ref "LED20") (pin "A") (pinfunction "A_A") (pintype "passive"))
      (node (ref "LED79") (pin "A") (pinfunction "A_A") (pintype "passive"))
      (node (ref "LED80") (pin "A") (pinfunction "A_A") (pintype "passive"))
      (node (ref "U1") (pin "35") (pinfunction "PC0_35") (pintype "bidirectional"))
    )
    (net (code "13") (name "LED_ANODE_21_22") (class "Default")
      (node (ref "LED125") (pin "A") (pinfunction "A_A") (pintype "passive"))
      (node (ref "LED21") (pin "A") (pinfunction "A_A") (pintype "passive"))
      (node (ref "LED22") (pin "A") (pinfunction "A_A") (pintype "passive"))
      (node (ref "LED81") (pin "A") (pinfunction "A_A") (pintype "passive"))
      (node (ref "LED82") (pin "A") (pinfunction "A_A") (pintype "passive"))
      (node (ref "U1") (pin "34") (pinfunction "PG1_34") (pintype "bidirectional"))
    )
    (net (code "14") (name "LED_ANODE_23_24") (class "Default")
      (node (ref "LED23") (pin "A") (pinfunction "A_A") (pintype "passive"))
      (node (ref "LED24") (pin "A") (pinfunction "A_A") (pintype "passive"))
      (node (ref "LED83") (pin "A") (pinfunction "A_A") (pintype "passive"))
      (node (ref "LED84") (pin "A") (pinfunction "A_A") (pintype "passive"))
      (node (ref "U1") (pin "33") (pinfunction "PG0_33") (pintype "bidirectional"))
    )
    (net (code "15") (name "LED_ANODE_25_26") (class "Default")
      (node (ref "LED126") (pin "A") (pinfunction "A_A") (pintype "passive"))
      (node (ref "LED25") (pin "A") (pinfunction "A_A") (pintype "passive"))
      (node (ref "LED26") (pin "A") (pinfunction "A_A") (pintype "passive"))
      (node (ref "LED85") (pin "A") (pinfunction "A_A") (pintype "passive"))
      (node (ref "LED86") (pin "A") (pinfunction "A_A") (pintype "passive"))
      (node (ref "U1") (pin "32") (pinfunction "PD7_32") (pintype "bidirectional"))
    )
    (net (code "16") (name "LED_ANODE_27_28") (class "Default")
      (node (ref "LED27") (pin "A") (pinfunction "A_A") (pintype "passive"))
      (node (ref "LED28") (pin "A") (pinfunction "A_A") (pintype "passive"))
      (node (ref "LED87") (pin "A") (pinfunction "A_A") (pintype "passive"))
      (node (ref "LED88") (pin "A") (pinfunction "A_A") (pintype "passive"))
      (node (ref "U1") (pin "31") (pinfunction "PD6_31") (pintype "bidirectional"))
    )
    (net (code "17") (name "LED_ANODE_29_30") (class "Default")
      (node (ref "LED29") (pin "A") (pinfunction "A_A") (pintype "passive"))
      (node (ref "LED30") (pin "A") (pinfunction "A_A") (pintype "passive"))
      (node (ref "LED89") (pin "A") (pinfunction "A_A") (pintype "passive"))
      (node (ref "LED90") (pin "A") (pinfunction "A_A") (pintype "passive"))
      (node (ref "U1") (pin "30") (pinfunction "PD5_30") (pintype "bidirectional"))
    )
    (net (code "18") (name "LED_ANODE_31_32") (class "Default")
      (node (ref "LED127") (pin "A") (pinfunction "A_A") (pintype "passive"))
      (node (ref "LED31") (pin "A") (pinfunction "A_A") (pintype "passive"))
      (node (ref "LED32") (pin "A") (pinfunction "A_A") (pintype "passive"))
      (node (ref "LED91") (pin "A") (pinfunction "A_A") (pintype "passive"))
      (node (ref "LED92") (pin "A") (pinfunction "A_A") (pintype "passive"))
      (node (ref "U1") (pin "19") (pinfunction "PG4_19") (pintype "bidirectional"))
    )
    (net (code "19") (name "LED_ANODE_33_34") (class "Default")
      (node (ref "LED33") (pin "A") (pinfunction "A_A") (pintype "passive"))
      (node (ref "LED34") (pin "A") (pinfunction "A_A") (pintype "passive"))
      (node (ref "LED93") (pin "A") (pinfunction "A_A") (pintype "passive"))
      (node (ref "LED94") (pin "A") (pinfunction "A_A") (pintype "passive"))
      (node (ref "U1") (pin "18") (pinfunction "PG3_18") (pintype "bidirectional"))
    )
    (net (code "20") (name "LED_ANODE_35_36") (class "Default")
      (node (ref "LED128") (pin "A") (pinfunction "A_A") (pintype "passive"))
      (node (ref "LED35") (pin "A") (pinfunction "A_A") (pintype "passive"))
      (node (ref "LED36") (pin "A") (pinfunction "A_A") (pintype "passive"))
      (node (ref "LED95") (pin "A") (pinfunction "A_A") (pintype "passive"))
      (node (ref "LED96") (pin "A") (pinfunction "A_A") (pintype "passive"))
      (node (ref "U1") (pin "17") (pinfunction "PB7_17") (pintype "bidirectional"))
    )
    (net (code "21") (name "LED_ANODE_37_38") (class "Default")
      (node (ref "LED37") (pin "A") (pinfunction "A_A") (pintype "passive"))
      (node (ref "LED38") (pin "A") (pinfunction "A_A") (pintype "passive"))
      (node (ref "LED97") (pin "A") (pinfunction "A_A") (pintype "passive"))
      (node (ref "LED98") (pin "A") (pinfunction "A_A") (pintype "passive"))
      (node (ref "U1") (pin "16") (pinfunction "PB6_16") (pintype "bidirectional"))
    )
    (net (code "22") (name "LED_ANODE_39_40") (class "Default")
      (node (ref "LED100") (pin "A") (pinfunction "A_A") (pintype "passive"))
      (node (ref "LED39") (pin "A") (pinfunction "A_A") (pintype "passive"))
      (node (ref "LED40") (pin "A") (pinfunction "A_A") (pintype "passive"))
      (node (ref "LED99") (pin "A") (pinfunction "A_A") (pintype "passive"))
      (node (ref "U1") (pin "15") (pinfunction "PB5_15") (pintype "bidirectional"))
    )
    (net (code "23") (name "LED_ANODE_41_42") (class "Default")
      (node (ref "LED101") (pin "A") (pinfunction "A_A") (pintype "passive"))
      (node (ref "LED102") (pin "A") (pinfunction "A_A") (pintype "passive"))
      (node (ref "LED129") (pin "A") (pinfunction "A_A") (pintype "passive"))
      (node (ref "LED41") (pin "A") (pinfunction "A_A") (pintype "passive"))
      (node (ref "LED42") (pin "A") (pinfunction "A_A") (pintype "passive"))
      (node (ref "U1") (pin "14") (pinfunction "PB4_14") (pintype "bidirectional"))
    )
    (net (code "24") (name "LED_ANODE_43_44") (class "Default")
      (node (ref "LED103") (pin "A") (pinfunction "A_A") (pintype "passive"))
      (node (ref "LED104") (pin "A") (pinfunction "A_A") (pintype "passive"))
      (node (ref "LED43") (pin "A") (pinfunction "A_A") (pintype "passive"))
      (node (ref "LED44") (pin "A") (pinfunction "A_A") (pintype "passive"))
      (node (ref "U1") (pin "10") (pinfunction "PB0_10") (pintype "bidirectional"))
    )
    (net (code "25") (name "LED_ANODE_45_46") (class "Default")
      (node (ref "LED105") (pin "A") (pinfunction "A_A") (pintype "passive"))
      (node (ref "LED106") (pin "A") (pinfunction "A_A") (pintype "passive"))
      (node (ref "LED130") (pin "A") (pinfunction "A_A") (pintype "passive"))
      (node (ref "LED45") (pin "A") (pinfunction "A_A") (pintype "passive"))
      (node (ref "LED46") (pin "A") (pinfunction "A_A") (pintype "passive"))
      (node (ref "U1") (pin "9") (pinfunction "PE7_9") (pintype "bidirectional"))
    )
    (net (code "26") (name "LED_ANODE_47_48") (class "Default")
      (node (ref "LED107") (pin "A") (pinfunction "A_A") (pintype "passive"))
      (node (ref "LED108") (pin "A") (pinfunction "A_A") (pintype "passive"))
      (node (ref "LED47") (pin "A") (pinfunction "A_A") (pintype "passive"))
      (node (ref "LED48") (pin "A") (pinfunction "A_A") (pintype "passive"))
      (node (ref "U1") (pin "8") (pinfunction "PE6_8") (pintype "bidirectional"))
    )
    (net (code "27") (name "LED_ANODE_49_50") (class "Default")
      (node (ref "LED109") (pin "A") (pinfunction "A_A") (pintype "passive"))
      (node (ref "LED110") (pin "A") (pinfunction "A_A") (pintype "passive"))
      (node (ref "LED49") (pin "A") (pinfunction "A_A") (pintype "passive"))
      (node (ref "LED50") (pin "A") (pinfunction "A_A") (pintype "passive"))
      (node (ref "U1") (pin "7") (pinfunction "PE5_7") (pintype "bidirectional"))
    )
    (net (code "28") (name "LED_ANODE_51_52") (class "Default")
      (node (ref "LED111") (pin "A") (pinfunction "A_A") (pintype "passive"))
      (node (ref "LED112") (pin "A") (pinfunction "A_A") (pintype "passive"))
      (node (ref "LED131") (pin "A") (pinfunction "A_A") (pintype "passive"))
      (node (ref "LED51") (pin "A") (pinfunction "A_A") (pintype "passive"))
      (node (ref "LED52") (pin "A") (pinfunction "A_A") (pintype "passive"))
      (node (ref "U1") (pin "6") (pinfunction "PE4_6") (pintype "bidirectional"))
    )
    (net (code "29") (name "LED_ANODE_53_54") (class "Default")
      (node (ref "LED113") (pin "A") (pinfunction "A_A") (pintype "passive"))
      (node (ref "LED114") (pin "A") (pinfunction "A_A") (pintype "passive"))
      (node (ref "LED53") (pin "A") (pinfunction "A_A") (pintype "passive"))
      (node (ref "LED54") (pin "A") (pinfunction "A_A") (pintype "passive"))
      (node (ref "U1") (pin "5") (pinfunction "PE3_5") (pintype "bidirectional"))
    )
    (net (code "30") (name "LED_ANODE_55_56") (class "Default")
      (node (ref "LED115") (pin "A") (pinfunction "A_A") (pintype "passive"))
      (node (ref "LED116") (pin "A") (pinfunction "A_A") (pintype "passive"))
      (node (ref "LED132") (pin "A") (pinfunction "A_A") (pintype "passive"))
      (node (ref "LED55") (pin "A") (pinfunction "A_A") (pintype "passive"))
      (node (ref "LED56") (pin "A") (pinfunction "A_A") (pintype "passive"))
      (node (ref "U1") (pin "4") (pinfunction "PE2_4") (pintype "bidirectional"))
    )
    (net (code "31") (name "LED_ANODE_57_58") (class "Default")
      (node (ref "LED117") (pin "A") (pinfunction "A_A") (pintype "passive"))
      (node (ref "LED118") (pin "A") (pinfunction "A_A") (pintype "passive"))
      (node (ref "LED57") (pin "A") (pinfunction "A_A") (pintype "passive"))
      (node (ref "LED58") (pin "A") (pinfunction "A_A") (pintype "passive"))
      (node (ref "U1") (pin "3") (pinfunction "PE1_3") (pintype "bidirectional"))
    )
    (net (code "32") (name "LED_ANODE_59_60") (class "Default")
      (node (ref "LED119") (pin "A") (pinfunction "A_A") (pintype "passive"))
      (node (ref "LED120") (pin "A") (pinfunction "A_A") (pintype "passive"))
      (node (ref "LED59") (pin "A") (pinfunction "A_A") (pintype "passive"))
      (node (ref "LED60") (pin "A") (pinfunction "A_A") (pintype "passive"))
      (node (ref "U1") (pin "2") (pinfunction "PE0_2") (pintype "bidirectional"))
    )
    (net (code "33") (name "LED_CATHODE_H") (class "Default")
      (node (ref "LED121") (pin "C") (pinfunction "C_C") (pintype "passive"))
      (node (ref "LED122") (pin "C") (pinfunction "C_C") (pintype "passive"))
      (node (ref "LED123") (pin "C") (pinfunction "C_C") (pintype "passive"))
      (node (ref "LED124") (pin "C") (pinfunction "C_C") (pintype "passive"))
      (node (ref "LED125") (pin "C") (pinfunction "C_C") (pintype "passive"))
      (node (ref "LED126") (pin "C") (pinfunction "C_C") (pintype "passive"))
      (node (ref "LED127") (pin "C") (pinfunction "C_C") (pintype "passive"))
      (node (ref "LED128") (pin "C") (pinfunction "C_C") (pintype "passive"))
      (node (ref "LED129") (pin "C") (pinfunction "C_C") (pintype "passive"))
      (node (ref "LED130") (pin "C") (pinfunction "C_C") (pintype "passive"))
      (node (ref "LED131") (pin "C") (pinfunction "C_C") (pintype "passive"))
      (node (ref "LED132") (pin "C") (pinfunction "C_C") (pintype "passive"))
      (node (ref "R3") (pin "1") (pinfunction "1_1") (pintype "passive"))
    )
    (net (code "34") (name "LED_CATHODE_M1") (class "Default")
      (node (ref "LED101") (pin "C") (pinfunction "C_C") (pintype "passive"))
      (node (ref "LED103") (pin "C") (pinfunction "C_C") (pintype "passive"))
      (node (ref "LED105") (pin "C") (pinfunction "C_C") (pintype "passive"))
      (node (ref "LED107") (pin "C") (pinfunction "C_C") (pintype "passive"))
      (node (ref "LED109") (pin "C") (pinfunction "C_C") (pintype "passive"))
      (node (ref "LED111") (pin "C") (pinfunction "C_C") (pintype "passive"))
      (node (ref "LED113") (pin "C") (pinfunction "C_C") (pintype "passive"))
      (node (ref "LED115") (pin "C") (pinfunction "C_C") (pintype "passive"))
      (node (ref "LED117") (pin "C") (pinfunction "C_C") (pintype "passive"))
      (node (ref "LED119") (pin "C") (pinfunction "C_C") (pintype "passive"))
      (node (ref "LED61") (pin "C") (pinfunction "C_C") (pintype "passive"))
      (node (ref "LED63") (pin "C") (pinfunction "C_C") (pintype "passive"))
      (node (ref "LED65") (pin "C") (pinfunction "C_C") (pintype "passive"))
      (node (ref "LED67") (pin "C") (pinfunction "C_C") (pintype "passive"))
      (node (ref "LED69") (pin "C") (pinfunction "C_C") (pintype "passive"))
      (node (ref "LED71") (pin "C") (pinfunction "C_C") (pintype "passive"))
      (node (ref "LED73") (pin "C") (pinfunction "C_C") (pintype "passive"))
      (node (ref "LED75") (pin "C") (pinfunction "C_C") (pintype "passive"))
      (node (ref "LED77") (pin "C") (pinfunction "C_C") (pintype "passive"))
      (node (ref "LED79") (pin "C") (pinfunction "C_C") (pintype "passive"))
      (node (ref "LED81") (pin "C") (pinfunction "C_C") (pintype "passive"))
      (node (ref "LED83") (pin "C") (pinfunction "C_C") (pintype "passive"))
      (node (ref "LED85") (pin "C") (pinfunction "C_C") (pintype "passive"))
      (node (ref "LED87") (pin "C") (pinfunction "C_C") (pintype "passive"))
      (node (ref "LED89") (pin "C") (pinfunction "C_C") (pintype "passive"))
      (node (ref "LED91") (pin "C") (pinfunction "C_C") (pintype "passive"))
      (node (ref "LED93") (pin "C") (pinfunction "C_C") (pintype "passive"))
      (node (ref "LED95") (pin "C") (pinfunction "C_C") (pintype "passive"))
      (node (ref "LED97") (pin "C") (pinfunction "C_C") (pintype "passive"))
      (node (ref "LED99") (pin "C") (pinfunction "C_C") (pintype "passive"))
      (node (ref "R5") (pin "1") (pinfunction "1_1") (pintype "passive"))
    )
    (net (code "35") (name "LED_CATHODE_M2") (class "Default")
      (node (ref "LED100") (pin "C") (pinfunction "C_C") (pintype "passive"))
      (node (ref "LED102") (pin "C") (pinfunction "C_C") (pintype "passive"))
      (node (ref "LED104") (pin "C") (pinfunction "C_C") (pintype "passive"))
      (node (ref "LED106") (pin "C") (pinfunction "C_C") (pintype "passive"))
      (node (ref "LED108") (pin "C") (pinfunction "C_C") (pintype "passive"))
      (node (ref "LED110") (pin "C") (pinfunction "C_C") (pintype "passive"))
      (node (ref "LED112") (pin "C") (pinfunction "C_C") (pintype "passive"))
      (node (ref "LED114") (pin "C") (pinfunction "C_C") (pintype "passive"))
      (node (ref "LED116") (pin "C") (pinfunction "C_C") (pintype "passive"))
      (node (ref "LED118") (pin "C") (pinfunction "C_C") (pintype "passive"))
      (node (ref "LED120") (pin "C") (pinfunction "C_C") (pintype "passive"))
      (node (ref "LED62") (pin "C") (pinfunction "C_C") (pintype "passive"))
      (node (ref "LED64") (pin "C") (pinfunction "C_C") (pintype "passive"))
      (node (ref "LED66") (pin "C") (pinfunction "C_C") (pintype "passive"))
      (node (ref "LED68") (pin "C") (pinfunction "C_C") (pintype "passive"))
      (node (ref "LED70") (pin "C") (pinfunction "C_C") (pintype "passive"))
      (node (ref "LED72") (pin "C") (pinfunction "C_C") (pintype "passive"))
      (node (ref "LED74") (pin "C") (pinfunction "C_C") (pintype "passive"))
      (node (ref "LED76") (pin "C") (pinfunction "C_C") (pintype "passive"))
      (node (ref "LED78") (pin "C") (pinfunction "C_C") (pintype "passive"))
      (node (ref "LED80") (pin "C") (pinfunction "C_C") (pintype "passive"))
      (node (ref "LED82") (pin "C") (pinfunction "C_C") (pintype "passive"))
      (node (ref "LED84") (pin "C") (pinfunction "C_C") (pintype "passive"))
      (node (ref "LED86") (pin "C") (pinfunction "C_C") (pintype "passive"))
      (node (ref "LED88") (pin "C") (pinfunction "C_C") (pintype "passive"))
      (node (ref "LED90") (pin "C") (pinfunction "C_C") (pintype "passive"))
      (node (ref "LED92") (pin "C") (pinfunction "C_C") (pintype "passive"))
      (node (ref "LED94") (pin "C") (pinfunction "C_C") (pintype "passive"))
      (node (ref "LED96") (pin "C") (pinfunction "C_C") (pintype "passive"))
      (node (ref "LED98") (pin "C") (pinfunction "C_C") (pintype "passive"))
      (node (ref "R4") (pin "1") (pinfunction "1_1") (pintype "passive"))
    )
    (net (code "36") (name "LED_CATHODE_S1") (class "Default")
      (node (ref "LED1") (pin "C") (pinfunction "C_C") (pintype "passive"))
      (node (ref "LED11") (pin "C") (pinfunction "C_C") (pintype "passive"))
      (node (ref "LED13") (pin "C") (pinfunction "C_C") (pintype "passive"))
      (node (ref "LED15") (pin "C") (pinfunction "C_C") (pintype "passive"))
      (node (ref "LED17") (pin "C") (pinfunction "C_C") (pintype "passive"))
      (node (ref "LED19") (pin "C") (pinfunction "C_C") (pintype "passive"))
      (node (ref "LED21") (pin "C") (pinfunction "C_C") (pintype "passive"))
      (node (ref "LED23") (pin "C") (pinfunction "C_C") (pintype "passive"))
      (node (ref "LED25") (pin "C") (pinfunction "C_C") (pintype "passive"))
      (node (ref "LED27") (pin "C") (pinfunction "C_C") (pintype "passive"))
      (node (ref "LED29") (pin "C") (pinfunction "C_C") (pintype "passive"))
      (node (ref "LED3") (pin "C") (pinfunction "C_C") (pintype "passive"))
      (node (ref "LED31") (pin "C") (pinfunction "C_C") (pintype "passive"))
      (node (ref "LED33") (pin "C") (pinfunction "C_C") (pintype "passive"))
      (node (ref "LED35") (pin "C") (pinfunction "C_C") (pintype "passive"))
      (node (ref "LED37") (pin "C") (pinfunction "C_C") (pintype "passive"))
      (node (ref "LED39") (pin "C") (pinfunction "C_C") (pintype "passive"))
      (node (ref "LED41") (pin "C") (pinfunction "C_C") (pintype "passive"))
      (node (ref "LED43") (pin "C") (pinfunction "C_C") (pintype "passive"))
      (node (ref "LED45") (pin "C") (pinfunction "C_C") (pintype "passive"))
      (node (ref "LED47") (pin "C") (pinfunction "C_C") (pintype "passive"))
      (node (ref "LED49") (pin "C") (pinfunction "C_C") (pintype "passive"))
      (node (ref "LED5") (pin "C") (pinfunction "C_C") (pintype "passive"))
      (node (ref "LED51") (pin "C") (pinfunction "C_C") (pintype "passive"))
      (node (ref "LED53") (pin "C") (pinfunction "C_C") (pintype "passive"))
      (node (ref "LED55") (pin "C") (pinfunction "C_C") (pintype "passive"))
      (node (ref "LED57") (pin "C") (pinfunction "C_C") (pintype "passive"))
      (node (ref "LED59") (pin "C") (pinfunction "C_C") (pintype "passive"))
      (node (ref "LED7") (pin "C") (pinfunction "C_C") (pintype "passive"))
      (node (ref "LED9") (pin "C") (pinfunction "C_C") (pintype "passive"))
      (node (ref "R2") (pin "1") (pinfunction "1_1") (pintype "passive"))
    )
    (net (code "37") (name "LED_CATHODE_S2") (class "Default")
      (node (ref "LED10") (pin "C") (pinfunction "C_C") (pintype "passive"))
      (node (ref "LED12") (pin "C") (pinfunction "C_C") (pintype "passive"))
      (node (ref "LED14") (pin "C") (pinfunction "C_C") (pintype "passive"))
      (node (ref "LED16") (pin "C") (pinfunction "C_C") (pintype "passive"))
      (node (ref "LED18") (pin "C") (pinfunction "C_C") (pintype "passive"))
      (node (ref "LED2") (pin "C") (pinfunction "C_C") (pintype "passive"))
      (node (ref "LED20") (pin "C") (pinfunction "C_C") (pintype "passive"))
      (node (ref "LED22") (pin "C") (pinfunction "C_C") (pintype "passive"))
      (node (ref "LED24") (pin "C") (pinfunction "C_C") (pintype "passive"))
      (node (ref "LED26") (pin "C") (pinfunction "C_C") (pintype "passive"))
      (node (ref "LED28") (pin "C") (pinfunction "C_C") (pintype "passive"))
      (node (ref "LED30") (pin "C") (pinfunction "C_C") (pintype "passive"))
      (node (ref "LED32") (pin "C") (pinfunction "C_C") (pintype "passive"))
      (node (ref "LED34") (pin "C") (pinfunction "C_C") (pintype "passive"))
      (node (ref "LED36") (pin "C") (pinfunction "C_C") (pintype "passive"))
      (node (ref "LED38") (pin "C") (pinfunction "C_C") (pintype "passive"))
      (node (ref "LED4") (pin "C") (pinfunction "C_C") (pintype "passive"))
      (node (ref "LED40") (pin "C") (pinfunction "C_C") (pintype "passive"))
      (node (ref "LED42") (pin "C") (pinfunction "C_C") (pintype "passive"))
      (node (ref "LED44") (pin "C") (pinfunction "C_C") (pintype "passive"))
      (node (ref "LED46") (pin "C") (pinfunction "C_C") (pintype "passive"))
      (node (ref "LED48") (pin "C") (pinfunction "C_C") (pintype "passive"))
      (node (ref "LED50") (pin "C") (pinfunction "C_C") (pintype "passive"))
      (node (ref "LED52") (pin "C") (pinfunction "C_C") (pintype "passive"))
      (node (ref "LED54") (pin "C") (pinfunction "C_C") (pintype "passive"))
      (node (ref "LED56") (pin "C") (pinfunction "C_C") (pintype "passive"))
      (node (ref "LED58") (pin "C") (pinfunction "C_C") (pintype "passive"))
      (node (ref "LED6") (pin "C") (pinfunction "C_C") (pintype "passive"))
      (node (ref "LED60") (pin "C") (pinfunction "C_C") (pintype "passive"))
      (node (ref "LED8") (pin "C") (pinfunction "C_C") (pintype "passive"))
      (node (ref "R1") (pin "1") (pinfunction "1_1") (pintype "passive"))
    )
    (net (code "38") (name "MOTOR") (class "Default")
      (node (ref "R8") (pin "1") (pinfunction "1_1") (pintype "passive"))
      (node (ref "R9") (pin "1") (pinfunction "1_1") (pintype "passive"))
      (node (ref "U1") (pin "45") (pinfunction "PA6_45") (pintype "bidirectional"))
    )
    (net (code "39") (name "Net-(AVRISP-MISO)") (class "Default")
      (node (ref "AVRISP") (pin "1") (pinfunction "MISO_1") (pintype "passive"))
      (node (ref "S1") (pin "P$1") (pinfunction "2_P$1") (pintype "passive"))
      (node (ref "U1") (pin "13") (pinfunction "PB3(MISO/PCINT11)_13") (pintype "bidirectional"))
    )
    (net (code "40") (name "Net-(AVRISP-MOSI)") (class "Default")
      (node (ref "AVRISP") (pin "4") (pinfunction "MOSI_4") (pintype "passive"))
      (node (ref "LED-CHG") (pin "C") (pinfunction "C_C") (pintype "passive"))
      (node (ref "U1") (pin "12") (pinfunction "PB2(MOSI/PCINT10)_12") (pintype "bidirectional"))
      (node (ref "U2") (pin "1") (pinfunction "STAT_1") (pintype "output"))
    )
    (net (code "41") (name "Net-(AVRISP-RST)") (class "Default")
      (node (ref "AVRISP") (pin "5") (pinfunction "RST_5") (pintype "passive"))
      (node (ref "U1") (pin "20") (pinfunction "/RESET_20") (pintype "bidirectional"))
    )
    (net (code "42") (name "Net-(AVRISP-SCK)") (class "Default")
      (node (ref "AVRISP") (pin "3") (pinfunction "SCK_3") (pintype "passive"))
      (node (ref "S2") (pin "3") (pinfunction "3_3") (pintype "passive"))
      (node (ref "S2") (pin "4") (pinfunction "4_4") (pintype "passive"))
      (node (ref "U1") (pin "11") (pinfunction "PB1(SCK/PCINT9)_11") (pintype "bidirectional"))
    )
    (net (code "43") (name "Net-(D1-A)") (class "Default")
      (node (ref "D1") (pin "2") (pinfunction "A_2") (pintype "passive"))
      (node (ref "M1") (pin "P$2") (pinfunction "P$2_P$2") (pintype "bidirectional"))
      (node (ref "Q3") (pin "3") (pinfunction "D_3") (pintype "passive"))
    )
    (net (code "44") (name "Net-(LED-CHG-PadA)") (class "Default")
      (node (ref "LED-CHG") (pin "A") (pinfunction "A_A") (pintype "passive"))
      (node (ref "R7") (pin "1") (pinfunction "1_1") (pintype "passive"))
    )
    (net (code "45") (name "Net-(Q2-P$1)") (class "Default")
      (node (ref "Q2") (pin "1") (pinfunction "P$1_1") (pintype "bidirectional"))
      (node (ref "U1") (pin "47") (pinfunction "PA4_47") (pintype "bidirectional"))
    )
    (net (code "46") (name "Net-(Q3-G)") (class "Default")
      (node (ref "Q3") (pin "1") (pinfunction "G_1") (pintype "passive"))
      (node (ref "R9") (pin "2") (pinfunction "2_2") (pintype "passive"))
    )
    (net (code "47") (name "Net-(U1-PA3)") (class "Default")
      (node (ref "U1") (pin "48") (pinfunction "PA3_48") (pintype "bidirectional"))
      (node (ref "U3") (pin "1") (pinfunction "OUT_1") (pintype "bidirectional"))
    )
    (net (code "48") (name "Net-(U1-PF0)") (class "Default")
      (node (ref "R1") (pin "2") (pinfunction "2_2") (pintype "passive"))
      (node (ref "U1") (pin "61") (pinfunction "PF0_61") (pintype "bidirectional"))
    )
    (net (code "49") (name "Net-(U1-PF1)") (class "Default")
      (node (ref "R2") (pin "2") (pinfunction "2_2") (pintype "passive"))
      (node (ref "U1") (pin "60") (pinfunction "PF1_60") (pintype "bidirectional"))
    )
    (net (code "50") (name "Net-(U1-PF2)") (class "Default")
      (node (ref "R3") (pin "2") (pinfunction "2_2") (pintype "passive"))
      (node (ref "U1") (pin "59") (pinfunction "PF2_59") (pintype "bidirectional"))
    )
    (net (code "51") (name "Net-(U1-PF4)") (class "Default")
      (node (ref "R4") (pin "2") (pinfunction "2_2") (pintype "passive"))
      (node (ref "U1") (pin "57") (pinfunction "PF4_57") (pintype "bidirectional"))
    )
    (net (code "52") (name "Net-(U1-PF5)") (class "Default")
      (node (ref "R5") (pin "2") (pinfunction "2_2") (pintype "passive"))
      (node (ref "U1") (pin "56") (pinfunction "PF5_56") (pintype "bidirectional"))
    )
    (net (code "53") (name "Net-(U1-XTAL1)") (class "Default")
      (node (ref "C3") (pin "1") (pinfunction "1_1") (pintype "passive"))
      (node (ref "Q1") (pin "2") (pinfunction "2_2") (pintype "bidirectional"))
      (node (ref "U1") (pin "24") (pinfunction "XTAL1_24") (pintype "bidirectional"))
    )
    (net (code "54") (name "Net-(U1-XTAL2)") (class "Default")
      (node (ref "C4") (pin "1") (pinfunction "1_1") (pintype "passive"))
      (node (ref "Q1") (pin "1") (pinfunction "1_1") (pintype "bidirectional"))
      (node (ref "U1") (pin "23") (pinfunction "XTAL2_23") (pintype "bidirectional"))
    )
    (net (code "55") (name "Net-(U2-PROG)") (class "Default")
      (node (ref "R6") (pin "2") (pinfunction "2_2") (pintype "passive"))
      (node (ref "U2") (pin "5") (pinfunction "PROG_5") (pintype "input"))
    )
    (net (code "56") (name "Net-(U2-VDD)") (class "Default")
      (node (ref "C5") (pin "+") (pinfunction "+_+") (pintype "passive"))
      (node (ref "R7") (pin "2") (pinfunction "2_2") (pintype "passive"))
      (node (ref "U2") (pin "4") (pinfunction "VDD_4") (pintype "power_in"))
      (node (ref "X1") (pin "1") (pinfunction "VBUS_1") (pintype "bidirectional"))
    )
    (net (code "57") (name "unconnected-(X1A-D+-Pad3)") (class "Default")
      (node (ref "X1") (pin "3") (pinfunction "D+_3") (pintype "bidirectional"))
    )
    (net (code "58") (name "unconnected-(X1A-D--Pad2)") (class "Default")
      (node (ref "X1") (pin "2") (pinfunction "D-_2") (pintype "bidirectional"))
    )
  )
)
